# Sheet6.net
KiCad netlist of a schematic drawn in Altium Designer
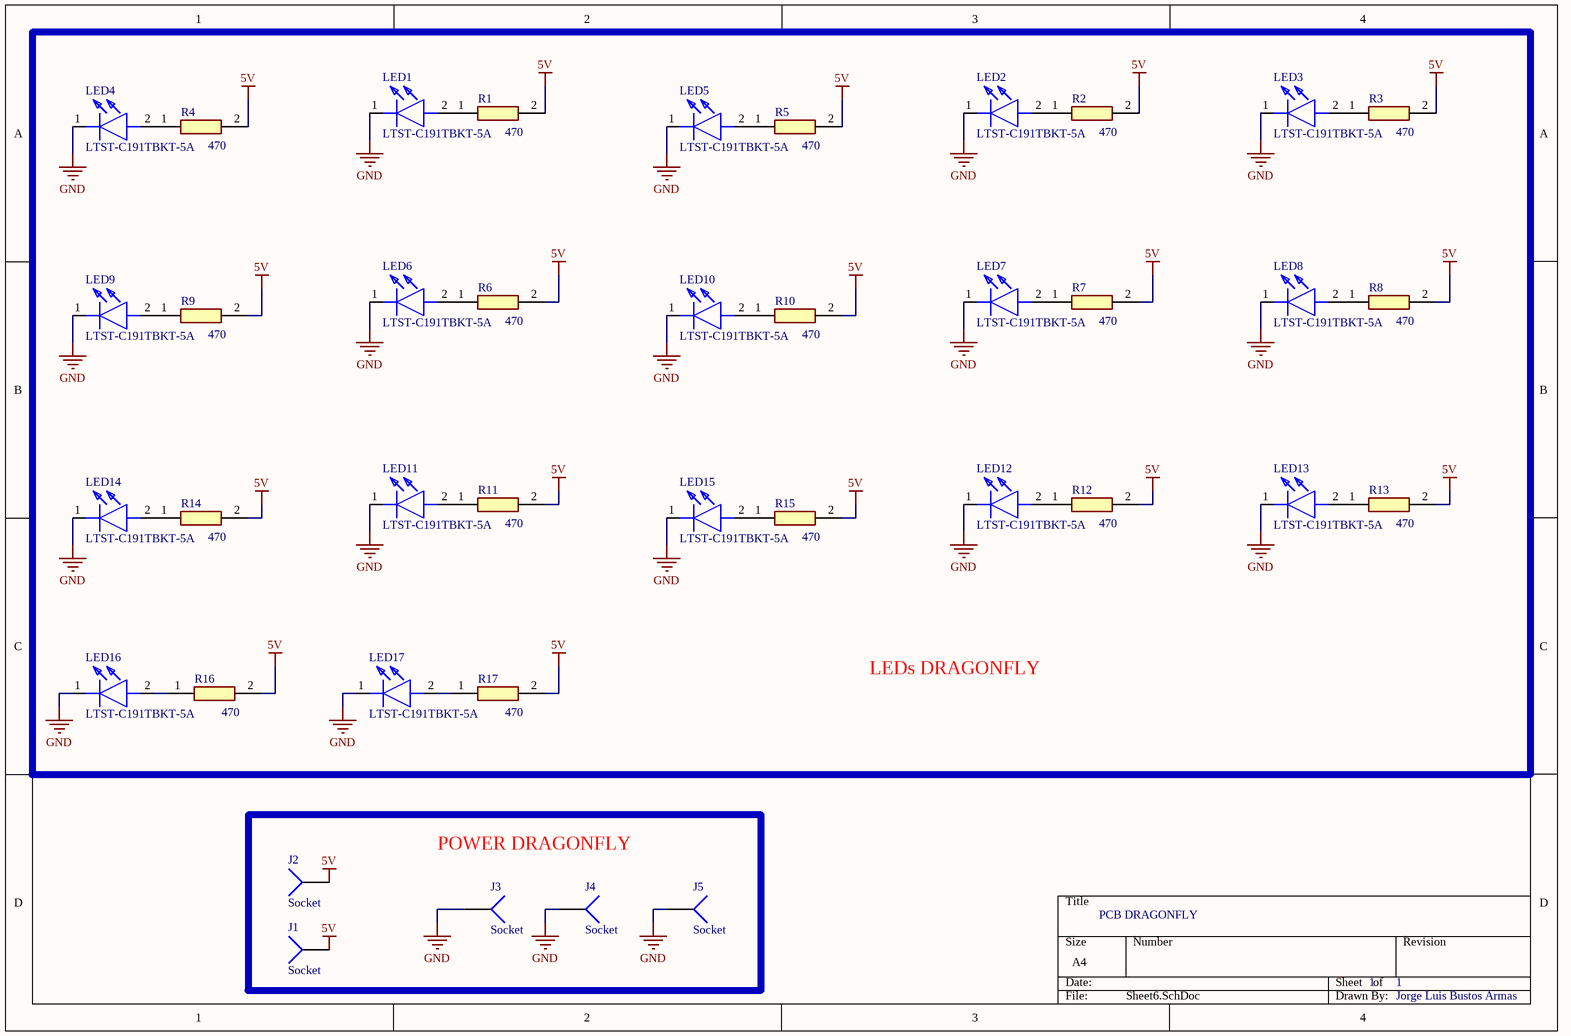
[diagram p0: Sheet6.SchDoc]

(export (version "E")
  (design (tool "Eeschema 10.0.6"))
  (components
    (comp (ref "J1")
      (value "Socket")
      (footprint "PIN1")
      (fields (field (name "PUBLISHER") "Altium Limited"))
      (libsource (lib "Miscellaneous Connectors") (part "Socket"))
    )
    (comp (ref "J2")
      (value "Socket")
      (footprint "PIN1")
      (fields (field (name "PUBLISHER") "Altium Limited"))
      (libsource (lib "Miscellaneous Connectors") (part "Socket"))
    )
    (comp (ref "J3")
      (value "Socket")
      (footprint "PIN1")
      (fields (field (name "PUBLISHER") "Altium Limited"))
      (libsource (lib "Miscellaneous Connectors") (part "Socket"))
    )
    (comp (ref "J4")
      (value "Socket")
      (footprint "PIN1")
      (fields (field (name "PUBLISHER") "Altium Limited"))
      (libsource (lib "Miscellaneous Connectors") (part "Socket"))
    )
    (comp (ref "J5")
      (value "Socket")
      (footprint "PIN1")
      (fields (field (name "PUBLISHER") "Altium Limited"))
      (libsource (lib "Miscellaneous Connectors") (part "Socket"))
    )
    (comp (ref "LED1")
      (value "LTST-C191TBKT-5A")
      (footprint "LEDC1608X60N")
      (description "LED")
      (fields (field (name "MOUSER PART NUMBER") "859-LTST-C191TBKT-5A"))
      (libsource (lib "SamacSys") (part "LTST-C191TBKT-5A"))
    )
    (comp (ref "LED2")
      (value "LTST-C191TBKT-5A")
      (footprint "LEDC1608X60N")
      (description "LED")
      (fields (field (name "MOUSER PART NUMBER") "859-LTST-C191TBKT-5A"))
      (libsource (lib "SamacSys") (part "LTST-C191TBKT-5A"))
    )
    (comp (ref "LED3")
      (value "LTST-C191TBKT-5A")
      (footprint "LEDC1608X60N")
      (description "LED")
      (fields (field (name "MOUSER PART NUMBER") "859-LTST-C191TBKT-5A"))
      (libsource (lib "SamacSys") (part "LTST-C191TBKT-5A"))
    )
    (comp (ref "LED4")
      (value "LTST-C191TBKT-5A")
      (footprint "LEDC1608X60N")
      (description "LED")
      (fields (field (name "MOUSER PART NUMBER") "859-LTST-C191TBKT-5A"))
      (libsource (lib "SamacSys") (part "LTST-C191TBKT-5A"))
    )
    (comp (ref "LED5")
      (value "LTST-C191TBKT-5A")
      (footprint "LEDC1608X60N")
      (description "LED")
      (fields (field (name "MOUSER PART NUMBER") "859-LTST-C191TBKT-5A"))
      (libsource (lib "SamacSys") (part "LTST-C191TBKT-5A"))
    )
    (comp (ref "LED6")
      (value "LTST-C191TBKT-5A")
      (footprint "LEDC1608X60N")
      (description "LED")
      (fields (field (name "MOUSER PART NUMBER") "859-LTST-C191TBKT-5A"))
      (libsource (lib "SamacSys") (part "LTST-C191TBKT-5A"))
    )
    (comp (ref "LED7")
      (value "LTST-C191TBKT-5A")
      (footprint "LEDC1608X60N")
      (description "LED")
      (fields (field (name "MOUSER PART NUMBER") "859-LTST-C191TBKT-5A"))
      (libsource (lib "SamacSys") (part "LTST-C191TBKT-5A"))
    )
    (comp (ref "LED8")
      (value "LTST-C191TBKT-5A")
      (footprint "LEDC1608X60N")
      (description "LED")
      (fields (field (name "MOUSER PART NUMBER") "859-LTST-C191TBKT-5A"))
      (libsource (lib "SamacSys") (part "LTST-C191TBKT-5A"))
    )
    (comp (ref "LED9")
      (value "LTST-C191TBKT-5A")
      (footprint "LEDC1608X60N")
      (description "LED")
      (fields (field (name "MOUSER PART NUMBER") "859-LTST-C191TBKT-5A"))
      (libsource (lib "SamacSys") (part "LTST-C191TBKT-5A"))
    )
    (comp (ref "LED10")
      (value "LTST-C191TBKT-5A")
      (footprint "LEDC1608X60N")
      (description "LED")
      (fields (field (name "MOUSER PART NUMBER") "859-LTST-C191TBKT-5A"))
      (libsource (lib "SamacSys") (part "LTST-C191TBKT-5A"))
    )
    (comp (ref "LED11")
      (value "LTST-C191TBKT-5A")
      (footprint "LEDC1608X60N")
      (description "LED")
      (fields (field (name "MOUSER PART NUMBER") "859-LTST-C191TBKT-5A"))
      (libsource (lib "SamacSys") (part "LTST-C191TBKT-5A"))
    )
    (comp (ref "LED12")
      (value "LTST-C191TBKT-5A")
      (footprint "LEDC1608X60N")
      (description "LED")
      (fields (field (name "MOUSER PART NUMBER") "859-LTST-C191TBKT-5A"))
      (libsource (lib "SamacSys") (part "LTST-C191TBKT-5A"))
    )
    (comp (ref "LED13")
      (value "LTST-C191TBKT-5A")
      (footprint "LEDC1608X60N")
      (description "LED")
      (fields (field (name "MOUSER PART NUMBER") "859-LTST-C191TBKT-5A"))
      (libsource (lib "SamacSys") (part "LTST-C191TBKT-5A"))
    )
    (comp (ref "LED14")
      (value "LTST-C191TBKT-5A")
      (footprint "LEDC1608X60N")
      (description "LED")
      (fields (field (name "MOUSER PART NUMBER") "859-LTST-C191TBKT-5A"))
      (libsource (lib "SamacSys") (part "LTST-C191TBKT-5A"))
    )
    (comp (ref "LED15")
      (value "LTST-C191TBKT-5A")
      (footprint "LEDC1608X60N")
      (description "LED")
      (fields (field (name "MOUSER PART NUMBER") "859-LTST-C191TBKT-5A"))
      (libsource (lib "SamacSys") (part "LTST-C191TBKT-5A"))
    )
    (comp (ref "LED16")
      (value "LTST-C191TBKT-5A")
      (footprint "LEDC1608X60N")
      (description "LED")
      (fields (field (name "MOUSER PART NUMBER") "859-LTST-C191TBKT-5A"))
      (libsource (lib "SamacSys") (part "LTST-C191TBKT-5A"))
    )
    (comp (ref "LED17")
      (value "LTST-C191TBKT-5A")
      (footprint "LEDC1608X60N")
      (description "LED")
      (fields (field (name "MOUSER PART NUMBER") "859-LTST-C191TBKT-5A"))
      (libsource (lib "SamacSys") (part "LTST-C191TBKT-5A"))
    )
    (comp (ref "R1")
      (value "470")
      (footprint "SamacSys:RESC1608X55N")
      (description "Resistor 1.5K")
      (fields
        (field (name "MANUFACTURER_PART_NUMBER") "KTR03EZPF1501")
        (field (name "MOUSER PART NUMBER") "755-KTR03EZPF1501")
      )
      (libsource (lib "SamacSys") (part "KTR03EZPF1501"))
    )
    (comp (ref "R2")
      (value "470")
      (footprint "SamacSys:RESC1608X55N")
      (description "Resistor 1.5K")
      (fields
        (field (name "MANUFACTURER_PART_NUMBER") "KTR03EZPF1501")
        (field (name "MOUSER PART NUMBER") "755-KTR03EZPF1501")
      )
      (libsource (lib "SamacSys") (part "KTR03EZPF1501"))
    )
    (comp (ref "R3")
      (value "470")
      (footprint "SamacSys:RESC1608X55N")
      (description "Resistor 1.5K")
      (fields
        (field (name "MANUFACTURER_PART_NUMBER") "KTR03EZPF1501")
        (field (name "MOUSER PART NUMBER") "755-KTR03EZPF1501")
      )
      (libsource (lib "SamacSys") (part "KTR03EZPF1501"))
    )
    (comp (ref "R4")
      (value "470")
      (footprint "SamacSys:RESC1608X55N")
      (description "Resistor 1.5K")
      (fields
        (field (name "MANUFACTURER_PART_NUMBER") "KTR03EZPF1501")
        (field (name "MOUSER PART NUMBER") "755-KTR03EZPF1501")
      )
      (libsource (lib "SamacSys") (part "KTR03EZPF1501"))
    )
    (comp (ref "R5")
      (value "470")
      (footprint "SamacSys:RESC1608X55N")
      (description "Resistor 1.5K")
      (fields
        (field (name "MANUFACTURER_PART_NUMBER") "KTR03EZPF1501")
        (field (name "MOUSER PART NUMBER") "755-KTR03EZPF1501")
      )
      (libsource (lib "SamacSys") (part "KTR03EZPF1501"))
    )
    (comp (ref "R6")
      (value "470")
      (footprint "SamacSys:RESC1608X55N")
      (description "Resistor 1.5K")
      (fields
        (field (name "MANUFACTURER_PART_NUMBER") "KTR03EZPF1501")
        (field (name "MOUSER PART NUMBER") "755-KTR03EZPF1501")
      )
      (libsource (lib "SamacSys") (part "KTR03EZPF1501"))
    )
    (comp (ref "R7")
      (value "470")
      (footprint "SamacSys:RESC1608X55N")
      (description "Resistor 1.5K")
      (fields
        (field (name "MANUFACTURER_PART_NUMBER") "KTR03EZPF1501")
        (field (name "MOUSER PART NUMBER") "755-KTR03EZPF1501")
      )
      (libsource (lib "SamacSys") (part "KTR03EZPF1501"))
    )
    (comp (ref "R8")
      (value "470")
      (footprint "SamacSys:RESC1608X55N")
      (description "Resistor 1.5K")
      (fields
        (field (name "MANUFACTURER_PART_NUMBER") "KTR03EZPF1501")
        (field (name "MOUSER PART NUMBER") "755-KTR03EZPF1501")
      )
      (libsource (lib "SamacSys") (part "KTR03EZPF1501"))
    )
    (comp (ref "R9")
      (value "470")
      (footprint "SamacSys:RESC1608X55N")
      (description "Resistor 1.5K")
      (fields
        (field (name "MANUFACTURER_PART_NUMBER") "KTR03EZPF1501")
        (field (name "MOUSER PART NUMBER") "755-KTR03EZPF1501")
      )
      (libsource (lib "SamacSys") (part "KTR03EZPF1501"))
    )
    (comp (ref "R10")
      (value "470")
      (footprint "SamacSys:RESC1608X55N")
      (description "Resistor 1.5K")
      (fields
        (field (name "MANUFACTURER_PART_NUMBER") "KTR03EZPF1501")
        (field (name "MOUSER PART NUMBER") "755-KTR03EZPF1501")
      )
      (libsource (lib "SamacSys") (part "KTR03EZPF1501"))
    )
    (comp (ref "R11")
      (value "470")
      (footprint "SamacSys:RESC1608X55N")
      (description "Resistor 1.5K")
      (fields
        (field (name "MANUFACTURER_PART_NUMBER") "KTR03EZPF1501")
        (field (name "MOUSER PART NUMBER") "755-KTR03EZPF1501")
      )
      (libsource (lib "SamacSys") (part "KTR03EZPF1501"))
    )
    (comp (ref "R12")
      (value "470")
      (footprint "SamacSys:RESC1608X55N")
      (description "Resistor 1.5K")
      (fields
        (field (name "MANUFACTURER_PART_NUMBER") "KTR03EZPF1501")
        (field (name "MOUSER PART NUMBER") "755-KTR03EZPF1501")
      )
      (libsource (lib "SamacSys") (part "KTR03EZPF1501"))
    )
    (comp (ref "R13")
      (value "470")
      (footprint "SamacSys:RESC1608X55N")
      (description "Resistor 1.5K")
      (fields
        (field (name "MANUFACTURER_PART_NUMBER") "KTR03EZPF1501")
        (field (name "MOUSER PART NUMBER") "755-KTR03EZPF1501")
      )
      (libsource (lib "SamacSys") (part "KTR03EZPF1501"))
    )
    (comp (ref "R14")
      (value "470")
      (footprint "SamacSys:RESC1608X55N")
      (description "Resistor 1.5K")
      (fields
        (field (name "MANUFACTURER_PART_NUMBER") "KTR03EZPF1501")
        (field (name "MOUSER PART NUMBER") "755-KTR03EZPF1501")
      )
      (libsource (lib "SamacSys") (part "KTR03EZPF1501"))
    )
    (comp (ref "R15")
      (value "470")
      (footprint "SamacSys:RESC1608X55N")
      (description "Resistor 1.5K")
      (fields
        (field (name "MANUFACTURER_PART_NUMBER") "KTR03EZPF1501")
        (field (name "MOUSER PART NUMBER") "755-KTR03EZPF1501")
      )
      (libsource (lib "SamacSys") (part "KTR03EZPF1501"))
    )
    (comp (ref "R16")
      (value "470")
      (footprint "SamacSys:RESC1608X55N")
      (description "Resistor 1.5K")
      (fields
        (field (name "MANUFACTURER_PART_NUMBER") "KTR03EZPF1501")
        (field (name "MOUSER PART NUMBER") "755-KTR03EZPF1501")
      )
      (libsource (lib "SamacSys") (part "KTR03EZPF1501"))
    )
    (comp (ref "R17")
      (value "470")
      (footprint "SamacSys:RESC1608X55N")
      (description "Resistor 1.5K")
      (fields
        (field (name "MANUFACTURER_PART_NUMBER") "KTR03EZPF1501")
        (field (name "MOUSER PART NUMBER") "755-KTR03EZPF1501")
      )
      (libsource (lib "SamacSys") (part "KTR03EZPF1501"))
    )
  )
  (nets
    (net (code "1") (name "5V") (class "Default")
      (node (ref "J1") (pin "1") (pinfunction "1_1") (pintype "passive"))
      (node (ref "J2") (pin "1") (pinfunction "1_1") (pintype "passive"))
      (node (ref "R1") (pin "2") (pinfunction "2_2") (pintype "passive"))
      (node (ref "R10") (pin "2") (pinfunction "2_2") (pintype "passive"))
      (node (ref "R11") (pin "2") (pinfunction "2_2") (pintype "passive"))
      (node (ref "R12") (pin "2") (pinfunction "2_2") (pintype "passive"))
      (node (ref "R13") (pin "2") (pinfunction "2_2") (pintype "passive"))
      (node (ref "R14") (pin "2") (pinfunction "2_2") (pintype "passive"))
      (node (ref "R15") (pin "2") (pinfunction "2_2") (pintype "passive"))
      (node (ref "R16") (pin "2") (pinfunction "2_2") (pintype "passive"))
      (node (ref "R17") (pin "2") (pinfunction "2_2") (pintype "passive"))
      (node (ref "R2") (pin "2") (pinfunction "2_2") (pintype "passive"))
      (node (ref "R3") (pin "2") (pinfunction "2_2") (pintype "passive"))
      (node (ref "R4") (pin "2") (pinfunction "2_2") (pintype "passive"))
      (node (ref "R5") (pin "2") (pinfunction "2_2") (pintype "passive"))
      (node (ref "R6") (pin "2") (pinfunction "2_2") (pintype "passive"))
      (node (ref "R7") (pin "2") (pinfunction "2_2") (pintype "passive"))
      (node (ref "R8") (pin "2") (pinfunction "2_2") (pintype "passive"))
      (node (ref "R9") (pin "2") (pinfunction "2_2") (pintype "passive"))
    )
    (net (code "2") (name "GND") (class "Default")
      (node (ref "J3") (pin "1") (pinfunction "1_1") (pintype "passive"))
      (node (ref "J4") (pin "1") (pinfunction "1_1") (pintype "passive"))
      (node (ref "J5") (pin "1") (pinfunction "1_1") (pintype "passive"))
      (node (ref "LED1") (pin "1") (pinfunction "K_1") (pintype "passive"))
      (node (ref "LED10") (pin "1") (pinfunction "K_1") (pintype "passive"))
      (node (ref "LED11") (pin "1") (pinfunction "K_1") (pintype "passive"))
      (node (ref "LED12") (pin "1") (pinfunction "K_1") (pintype "passive"))
      (node (ref "LED13") (pin "1") (pinfunction "K_1") (pintype "passive"))
      (node (ref "LED14") (pin "1") (pinfunction "K_1") (pintype "passive"))
      (node (ref "LED15") (pin "1") (pinfunction "K_1") (pintype "passive"))
      (node (ref "LED16") (pin "1") (pinfunction "K_1") (pintype "passive"))
      (node (ref "LED17") (pin "1") (pinfunction "K_1") (pintype "passive"))
      (node (ref "LED2") (pin "1") (pinfunction "K_1") (pintype "passive"))
      (node (ref "LED3") (pin "1") (pinfunction "K_1") (pintype "passive"))
      (node (ref "LED4") (pin "1") (pinfunction "K_1") (pintype "passive"))
      (node (ref "LED5") (pin "1") (pinfunction "K_1") (pintype "passive"))
      (node (ref "LED6") (pin "1") (pinfunction "K_1") (pintype "passive"))
      (node (ref "LED7") (pin "1") (pinfunction "K_1") (pintype "passive"))
      (node (ref "LED8") (pin "1") (pinfunction "K_1") (pintype "passive"))
      (node (ref "LED9") (pin "1") (pinfunction "K_1") (pintype "passive"))
    )
    (net (code "3") (name "Net-(LED1-A)") (class "Default")
      (node (ref "LED1") (pin "2") (pinfunction "A_2") (pintype "passive"))
      (node (ref "R1") (pin "1") (pinfunction "1_1") (pintype "passive"))
    )
    (net (code "4") (name "Net-(LED2-A)") (class "Default")
      (node (ref "LED2") (pin "2") (pinfunction "A_2") (pintype "passive"))
      (node (ref "R2") (pin "1") (pinfunction "1_1") (pintype "passive"))
    )
    (net (code "5") (name "Net-(LED3-A)") (class "Default")
      (node (ref "LED3") (pin "2") (pinfunction "A_2") (pintype "passive"))
      (node (ref "R3") (pin "1") (pinfunction "1_1") (pintype "passive"))
    )
    (net (code "6") (name "Net-(LED4-A)") (class "Default")
      (node (ref "LED4") (pin "2") (pinfunction "A_2") (pintype "passive"))
      (node (ref "R4") (pin "1") (pinfunction "1_1") (pintype "passive"))
    )
    (net (code "7") (name "Net-(LED5-A)") (class "Default")
      (node (ref "LED5") (pin "2") (pinfunction "A_2") (pintype "passive"))
      (node (ref "R5") (pin "1") (pinfunction "1_1") (pintype "passive"))
    )
    (net (code "8") (name "Net-(LED6-A)") (class "Default")
      (node (ref "LED6") (pin "2") (pinfunction "A_2") (pintype "passive"))
      (node (ref "R6") (pin "1") (pinfunction "1_1") (pintype "passive"))
    )
    (net (code "9") (name "Net-(LED7-A)") (class "Default")
      (node (ref "LED7") (pin "2") (pinfunction "A_2") (pintype "passive"))
      (node (ref "R7") (pin "1") (pinfunction "1_1") (pintype "passive"))
    )
    (net (code "10") (name "Net-(LED8-A)") (class "Default")
      (node (ref "LED8") (pin "2") (pinfunction "A_2") (pintype "passive"))
      (node (ref "R8") (pin "1") (pinfunction "1_1") (pintype "passive"))
    )
    (net (code "11") (name "Net-(LED9-A)") (class "Default")
      (node (ref "LED9") (pin "2") (pinfunction "A_2") (pintype "passive"))
      (node (ref "R9") (pin "1") (pinfunction "1_1") (pintype "passive"))
    )
    (net (code "12") (name "Net-(LED10-A)") (class "Default")
      (node (ref "LED10") (pin "2") (pinfunction "A_2") (pintype "passive"))
      (node (ref "R10") (pin "1") (pinfunction "1_1") (pintype "passive"))
    )
    (net (code "13") (name "Net-(LED11-A)") (class "Default")
      (node (ref "LED11") (pin "2") (pinfunction "A_2") (pintype "passive"))
      (node (ref "R11") (pin "1") (pinfunction "1_1") (pintype "passive"))
    )
    (net (code "14") (name "Net-(LED12-A)") (class "Default")
      (node (ref "LED12") (pin "2") (pinfunction "A_2") (pintype "passive"))
      (node (ref "R12") (pin "1") (pinfunction "1_1") (pintype "passive"))
    )
    (net (code "15") (name "Net-(LED13-A)") (class "Default")
      (node (ref "LED13") (pin "2") (pinfunction "A_2") (pintype "passive"))
      (node (ref "R13") (pin "1") (pinfunction "1_1") (pintype "passive"))
    )
    (net (code "16") (name "Net-(LED14-A)") (class "Default")
      (node (ref "LED14") (pin "2") (pinfunction "A_2") (pintype "passive"))
      (node (ref "R14") (pin "1") (pinfunction "1_1") (pintype "passive"))
    )
    (net (code "17") (name "Net-(LED15-A)") (class "Default")
      (node (ref "LED15") (pin "2") (pinfunction "A_2") (pintype "passive"))
      (node (ref "R15") (pin "1") (pinfunction "1_1") (pintype "passive"))
    )
    (net (code "18") (name "Net-(LED16-A)") (class "Default")
      (node (ref "LED16") (pin "2") (pinfunction "A_2") (pintype "passive"))
      (node (ref "R16") (pin "1") (pinfunction "1_1") (pintype "passive"))
    )
    (net (code "19") (name "Net-(LED17-A)") (class "Default")
      (node (ref "LED17") (pin "2") (pinfunction "A_2") (pintype "passive"))
      (node (ref "R17") (pin "1") (pinfunction "1_1") (pintype "passive"))
    )
  )
)
